# Motor-Z.net
KiCad netlist of a schematic drawn in Altium Designer
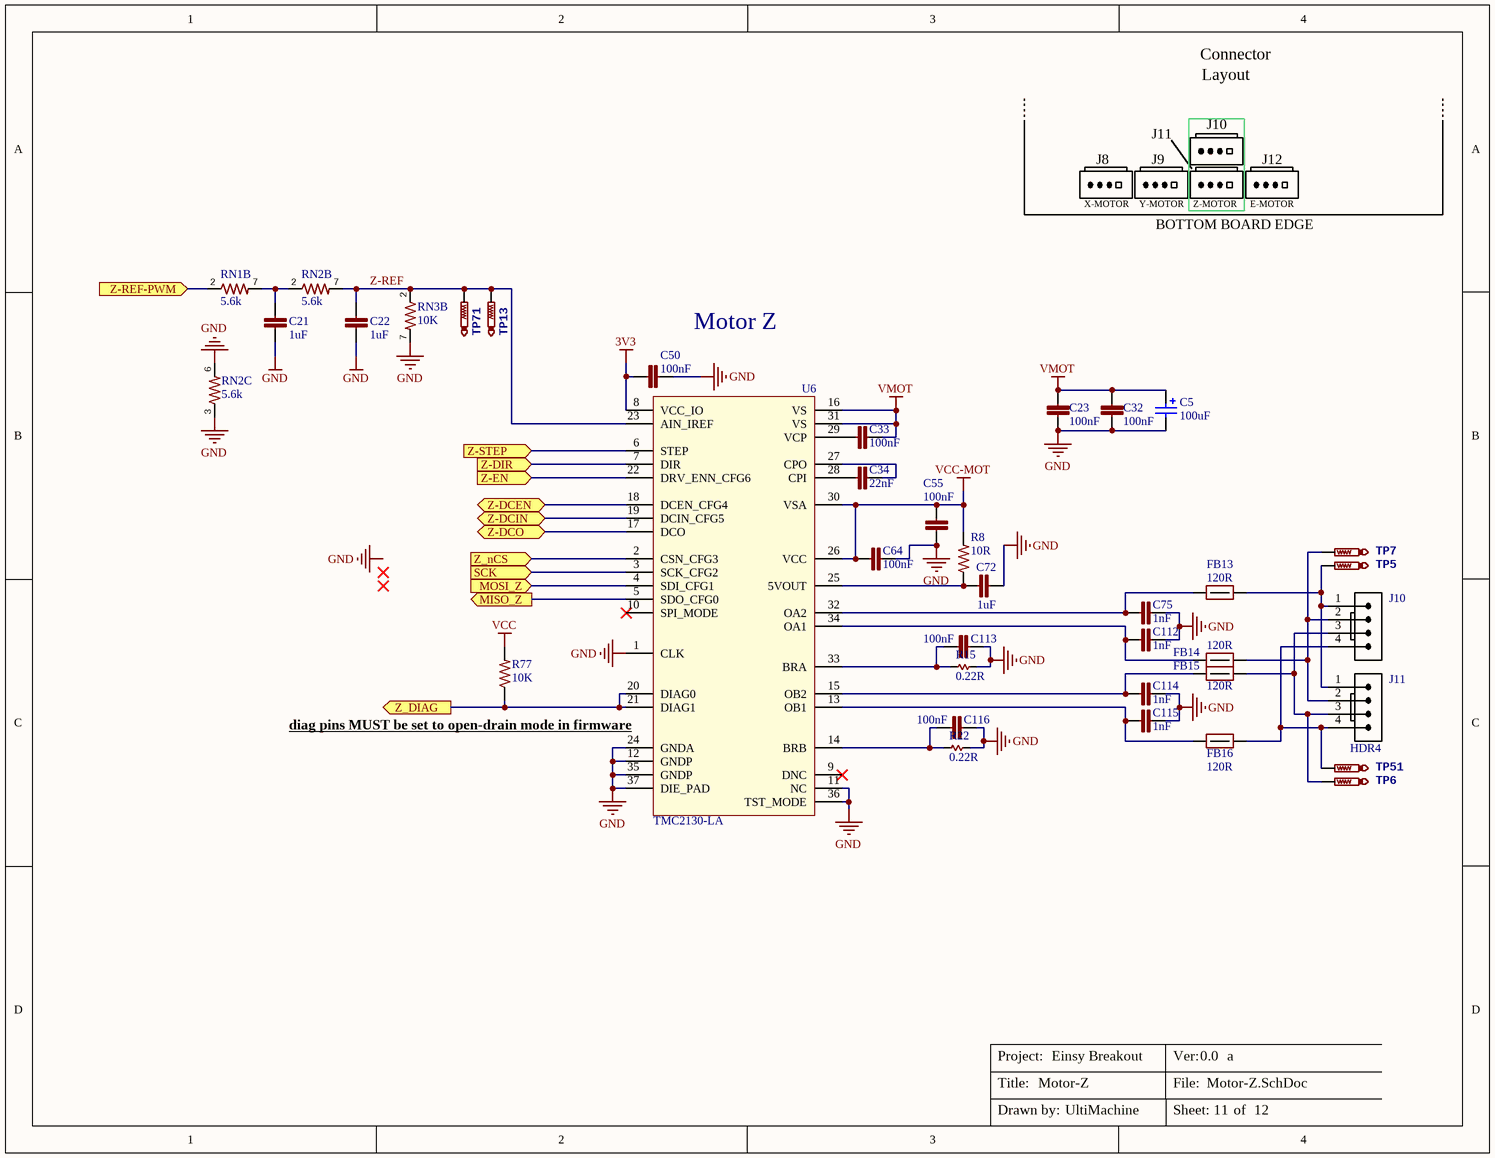
[diagram p0: Motor-Z.SchDoc]

(export (version "E")
  (design (tool "Eeschema 10.0.6"))
  (components
    (comp (ref "C5")
      (value "100uF")
      (footprint "CAP-ELEC-063063077")
      (description "CAP ALUM 100UF 35V 20% SMD")
      (fields (field (name "MANUFACTURER") "Nichicon") (field (name "TOLERANCE") "+/- 20%"))
      (libsource (lib "3Delight") (part "UWT1V101MCL1GS"))
    )
    (comp (ref "C21")
      (value "1uF")
      (footprint "C0402")
      (description "CAP CER 0402 1uF 6.3V 10% X5R")
      (fields (field (name "MANUFACTURER") "Murata") (field (name "TOLERANCE") "+/- 10%"))
      (libsource (lib "3Delight") (part "GRM155R60J105KE19D"))
    )
    (comp (ref "C22")
      (value "1uF")
      (footprint "C0402")
      (description "CAP CER 0402 1uF 6.3V 10% X5R")
      (fields (field (name "MANUFACTURER") "Murata") (field (name "TOLERANCE") "+/- 10%"))
      (libsource (lib "3Delight") (part "GRM155R60J105KE19D"))
    )
    (comp (ref "C23")
      (value "100nF")
      (footprint "C0603")
      (description "CAP CER 0603 100nF 50V 10% X7R")
      (fields (field (name "MANUFACTURER") "Kemet") (field (name "TOLERANCE") "+/- 10%"))
      (libsource (lib "3Delight") (part "C0603C104K5RACTU"))
    )
    (comp (ref "C32")
      (value "100nF")
      (footprint "C0603")
      (description "CAP CER 0603 100nF 50V 10% X7R")
      (fields (field (name "MANUFACTURER") "Kemet") (field (name "TOLERANCE") "+/- 10%"))
      (libsource (lib "3Delight") (part "C0603C104K5RACTU"))
    )
    (comp (ref "C33")
      (value "100nF")
      (footprint "C0603")
      (description "CAP CER 0603 100nF 50V 10% X7R")
      (fields (field (name "MANUFACTURER") "Kemet") (field (name "TOLERANCE") "+/- 10%"))
      (libsource (lib "") (part "C0603C104K5RACTU_1"))
    )
    (comp (ref "C34")
      (value "22nF")
      (footprint "C0402")
      (description "CAP CER 0402 22nF ±10% 50V X7R")
      (fields (field (name "MANUFACTURER") "YAGEO") (field (name "TOLERANCE") "+/- 10%"))
      (libsource (lib "3Delight") (part "GCM155R71H223KA55D"))
    )
    (comp (ref "C50")
      (value "100nF")
      (footprint "C0402")
      (description "CAP CER 0402 100nF 16V 10% X7R")
      (fields (field (name "MANUFACTURER") "Murata") (field (name "TOLERANCE") "+/- 10%"))
      (libsource (lib "3Delight") (part "GRM155R71C104KA88D"))
    )
    (comp (ref "C55")
      (value "100nF")
      (footprint "C0402")
      (description "CAP CER 0402 100nF 16V 10% X7R")
      (fields (field (name "MANUFACTURER") "Murata") (field (name "TOLERANCE") "+/- 10%"))
      (libsource (lib "") (part "GRM155R71C104KA88D_1"))
    )
    (comp (ref "C64")
      (value "100nF")
      (footprint "C0402")
      (description "CAP CER 0402 100nF 16V 10% X7R")
      (fields (field (name "MANUFACTURER") "Murata") (field (name "TOLERANCE") "+/- 10%"))
      (libsource (lib "3Delight") (part "GRM155R71C104KA88D"))
    )
    (comp (ref "C72")
      (value "1uF")
      (footprint "C0402")
      (description "CAP CER 0402 1uF 6.3V 10% X5R")
      (fields (field (name "MANUFACTURER") "Murata") (field (name "TOLERANCE") "+/- 10%"))
      (libsource (lib "") (part "GRM155R60J105KE19D_1"))
    )
    (comp (ref "C75")
      (value "1nF")
      (footprint "C0603")
      (description "CAP CER 0603  1nF 50v 10% X7R")
      (fields (field (name "MANUFACTURER") "Kemet") (field (name "TOLERANCE") "+/- 10%"))
      (libsource (lib "3Delight") (part "C0603C102K5RACTU"))
    )
    (comp (ref "C112")
      (value "1nF")
      (footprint "C0603")
      (description "CAP CER 0603  1nF 50v 10% X7R")
      (fields (field (name "MANUFACTURER") "Kemet") (field (name "TOLERANCE") "+/- 10%"))
      (libsource (lib "3Delight") (part "C0603C102K5RACTU"))
    )
    (comp (ref "C113")
      (value "100nF")
      (footprint "C0603")
      (description "CAP CER 0603 100nF 50V 10% X7R")
      (fields (field (name "MANUFACTURER") "Kemet") (field (name "TOLERANCE") "+/- 10%"))
      (libsource (lib "") (part "C0603C104K5RACTU_2"))
    )
    (comp (ref "C114")
      (value "1nF")
      (footprint "C0603")
      (description "CAP CER 0603  1nF 50v 10% X7R")
      (fields (field (name "MANUFACTURER") "Kemet") (field (name "TOLERANCE") "+/- 10%"))
      (libsource (lib "3Delight") (part "C0603C102K5RACTU"))
    )
    (comp (ref "C115")
      (value "1nF")
      (footprint "C0603")
      (description "CAP CER 0603  1nF 50v 10% X7R")
      (fields (field (name "MANUFACTURER") "Kemet") (field (name "TOLERANCE") "+/- 10%"))
      (libsource (lib "3Delight") (part "C0603C102K5RACTU"))
    )
    (comp (ref "C116")
      (value "100nF")
      (footprint "C0603")
      (description "CAP CER 0603 100nF 50V 10% X7R")
      (fields (field (name "MANUFACTURER") "Kemet") (field (name "TOLERANCE") "+/- 10%"))
      (libsource (lib "") (part "C0603C104K5RACTU_2"))
    )
    (comp (ref "FB13")
      (value "120R")
      (footprint "FB0603")
      (description "FERRITE BEAD 120 OHM 0603 1LN")
      (fields (field (name "MANUFACTURER") "Samsung") (field (name "PART") "FERRITE 120R 3A 0603"))
      (libsource (lib "Inductors") (part "FERRITE 120R 3A 0603"))
    )
    (comp (ref "FB14")
      (value "120R")
      (footprint "FB0603")
      (description "FERRITE BEAD 120 OHM 0603 1LN")
      (fields (field (name "MANUFACTURER") "Samsung") (field (name "PART") "FERRITE 120R 3A 0603"))
      (libsource (lib "Inductors") (part "FERRITE 120R 3A 0603"))
    )
    (comp (ref "FB15")
      (value "120R")
      (footprint "FB0603")
      (description "FERRITE BEAD 120 OHM 0603 1LN")
      (fields (field (name "MANUFACTURER") "Samsung") (field (name "PART") "FERRITE 120R 3A 0603"))
      (libsource (lib "Inductors") (part "FERRITE 120R 3A 0603"))
    )
    (comp (ref "FB16")
      (value "120R")
      (footprint "FB0603")
      (description "FERRITE BEAD 120 OHM 0603 1LN")
      (fields (field (name "MANUFACTURER") "Samsung") (field (name "PART") "FERRITE 120R 3A 0603"))
      (libsource (lib "Inductors") (part "FERRITE 120R 3A 0603"))
    )
    (comp (ref "J10")
      (value "Molex 0705430003")
      (footprint "4POL254")
      (description "Molex 4 Pin Clip Connector")
      (fields (field (name "MANUFACTURER") "Molex") (field (name "PART") "4 Pin Conn"))
      (libsource (lib "3Delight") (part "CONN 4PIN 0.1{dblquote} VERT SHRD LOCK ALT"))
    )
    (comp (ref "J11")
      (value "HDR4")
      (footprint "4POL254")
      (description "Molex 4 Pin Clip Connector")
      (fields (field (name "MANUFACTURER") "Molex") (field (name "PART") "4 Pin Conn"))
      (libsource (lib "3Delight") (part "CONN 4PIN 0.1{dblquote} VERT SHRD LOCK ALT"))
    )
    (comp (ref "R8")
      (value "10R")
      (footprint "R0402")
      (description "RES SMD 10 OHM 1% 1/16W 0402")
      (fields (field (name "MANUFACTURER") "Yageo") (field (name "TOLERANCE") "+/- 1%"))
      (libsource (lib "3Delight") (part "RC0402FR-0710RL"))
    )
    (comp (ref "R15")
      (value "0.22R")
      (footprint "R1206")
      (description "RES SMD 0.22 OHM 1% 1/3W 1206")
      (fields (field (name "MANUFACTURER") "Panasonic") (field (name "TOLERANCE") "+/- 1%"))
      (libsource (lib "Resistors") (part "0.22R 1% 1206"))
    )
    (comp (ref "R22")
      (value "0.22R")
      (footprint "R1206")
      (description "RES SMD 0.22 OHM 1% 1/3W 1206")
      (fields (field (name "MANUFACTURER") "Panasonic") (field (name "TOLERANCE") "+/- 1%"))
      (libsource (lib "Resistors") (part "0.22R 1% 1206"))
    )
    (comp (ref "R77")
      (value "10K")
      (footprint "R0402")
      (description "RES SMD 10K OHM 1% 1/16W 0402")
      (fields (field (name "MANUFACTURER") "Yageo") (field (name "PART") "10k 1% 0402"))
      (libsource (lib "3Delight") (part "RC0402FR-0710KP"))
    )
    (comp (ref "RN1")
      (value "5.6k")
      (footprint "CAY16")
      (description "RES ARRAY 4 RES 5.6K OHM 1206")
      (fields (field (name "MANUFACTURER") "Bourns") (field (name "TOLERANCE") "+/- 5%"))
      (libsource (lib "Resistors") (part "5.6k x 4 5% 1206"))
    )
    (comp (ref "RN2")
      (value "5.6k")
      (footprint "CAY16")
      (description "RES ARRAY 4 RES 5.6K OHM 1206")
      (fields (field (name "MANUFACTURER") "Bourns") (field (name "TOLERANCE") "+/- 5%"))
      (libsource (lib "Resistors") (part "5.6k x 4 5% 1206"))
    )
    (comp (ref "RN3")
      (value "10K")
      (footprint "CAY16")
      (description "RES ARRAY 4 RES 10K 1206 62.5mW 5%")
      (fields (field (name "MANUFACTURER") "Bourns") (field (name "TOLERANCE") "+/- 5%"))
      (libsource (lib "3Delight") (part "CAY16-103J4LF"))
    )
    (comp (ref "TP5")
      (value "TestPoint")
      (footprint "TP1-27")
      (description "Test Point")
      (libsource (lib "") (part "TestPoint_1"))
    )
    (comp (ref "TP6")
      (value "TestPoint")
      (footprint "TP1-27")
      (description "Test Point")
      (libsource (lib "") (part "TestPoint_1"))
    )
    (comp (ref "TP7")
      (value "TestPoint")
      (footprint "TP1-27")
      (description "Test Point")
      (libsource (lib "") (part "TestPoint_1"))
    )
    (comp (ref "TP13")
      (value "TestPoint")
      (footprint "TP1-27")
      (description "Test Point")
      (libsource (lib "3Delight") (part "TestPoint"))
    )
    (comp (ref "TP51")
      (value "TestPoint")
      (footprint "TP1-27")
      (description "Test Point")
      (libsource (lib "") (part "TestPoint_1"))
    )
    (comp (ref "TP71")
      (value "TestPoint")
      (footprint "TP1-27")
      (description "Test Point")
      (libsource (lib "3Delight") (part "TestPoint"))
    )
    (comp (ref "U6")
      (value "TMC2130-LA")
      (footprint "QFN36-50P500X600X900_HS-37N")
      (description "IC STEPPER MOTOR DVR SPI 36QFN")
      (fields (field (name "MANUFACTURER") "Trinamic") (field (name "PART") "TMC2130"))
      (libsource (lib "ICs-Motor Controller") (part "TMC2130-LA-T"))
    )
  )
  (nets
    (net (code "1") (name "/MISO_Z") (class "Default")
      (node (ref "U6") (pin "5") (pinfunction "SDO_CFG0_5") (pintype "passive"))
    )
    (net (code "2") (name "/MOSI_Z") (class "Default")
      (node (ref "U6") (pin "4") (pinfunction "SDI_CFG1_4") (pintype "passive"))
    )
    (net (code "3") (name "/SCK") (class "Default")
      (node (ref "U6") (pin "3") (pinfunction "SCK_CFG2_3") (pintype "passive"))
    )
    (net (code "4") (name "/Z-DCEN") (class "Default")
      (node (ref "U6") (pin "18") (pinfunction "DCEN_CFG4_18") (pintype "passive"))
    )
    (net (code "5") (name "/Z-DCIN") (class "Default")
      (node (ref "U6") (pin "19") (pinfunction "DCIN_CFG5_19") (pintype "passive"))
    )
    (net (code "6") (name "/Z-DCO") (class "Default")
      (node (ref "U6") (pin "17") (pinfunction "DCO_17") (pintype "passive"))
    )
    (net (code "7") (name "/Z-DIR") (class "Default")
      (node (ref "U6") (pin "7") (pinfunction "DIR_7") (pintype "passive"))
    )
    (net (code "8") (name "/Z-EN") (class "Default")
      (node (ref "U6") (pin "22") (pinfunction "DRV_ENN_CFG6_22") (pintype "passive"))
    )
    (net (code "9") (name "/Z-REF") (class "Default")
      (node (ref "C22") (pin "1") (pinfunction "1_1") (pintype "passive"))
      (node (ref "RN2") (pin "7") (pinfunction "2_7") (pintype "passive"))
      (node (ref "RN3") (pin "2") (pinfunction "1_2") (pintype "passive"))
      (node (ref "TP13") (pin "TP") (pinfunction "TP_TP") (pintype "passive"))
      (node (ref "TP71") (pin "TP") (pinfunction "TP_TP") (pintype "passive"))
      (node (ref "U6") (pin "23") (pinfunction "AIN_IREF_23") (pintype "passive"))
    )
    (net (code "10") (name "/Z-REF-PWM") (class "Default")
      (node (ref "RN1") (pin "2") (pinfunction "1_2") (pintype "passive"))
    )
    (net (code "11") (name "/Z-STEP") (class "Default")
      (node (ref "U6") (pin "6") (pinfunction "STEP_6") (pintype "passive"))
    )
    (net (code "12") (name "/Z_DIAG") (class "Default")
      (node (ref "R77") (pin "1") (pinfunction "1_1") (pintype "passive"))
      (node (ref "U6") (pin "20") (pinfunction "DIAG0_20") (pintype "passive"))
      (node (ref "U6") (pin "21") (pinfunction "DIAG1_21") (pintype "passive"))
    )
    (net (code "13") (name "/Z_nCS") (class "Default")
      (node (ref "U6") (pin "2") (pinfunction "CSN_CFG3_2") (pintype "passive"))
    )
    (net (code "14") (name "3V3") (class "Default")
      (node (ref "C50") (pin "2") (pinfunction "2_2") (pintype "passive"))
      (node (ref "U6") (pin "8") (pinfunction "VCC_IO_8") (pintype "passive"))
    )
    (net (code "15") (name "GND") (class "Default")
      (node (ref "C112") (pin "2") (pinfunction "2_2") (pintype "passive"))
      (node (ref "C113") (pin "1") (pinfunction "1_1") (pintype "passive"))
      (node (ref "C114") (pin "2") (pinfunction "2_2") (pintype "passive"))
      (node (ref "C115") (pin "2") (pinfunction "2_2") (pintype "passive"))
      (node (ref "C116") (pin "1") (pinfunction "1_1") (pintype "passive"))
      (node (ref "C21") (pin "2") (pinfunction "2_2") (pintype "passive"))
      (node (ref "C22") (pin "2") (pinfunction "2_2") (pintype "passive"))
      (node (ref "C23") (pin "1") (pinfunction "1_1") (pintype "passive"))
      (node (ref "C32") (pin "1") (pinfunction "1_1") (pintype "passive"))
      (node (ref "C5") (pin "2") (pinfunction "2_2") (pintype "passive"))
      (node (ref "C50") (pin "1") (pinfunction "1_1") (pintype "passive"))
      (node (ref "C55") (pin "1") (pinfunction "1_1") (pintype "passive"))
      (node (ref "C64") (pin "1") (pinfunction "1_1") (pintype "passive"))
      (node (ref "C72") (pin "2") (pinfunction "2_2") (pintype "passive"))
      (node (ref "C75") (pin "2") (pinfunction "2_2") (pintype "passive"))
      (node (ref "R15") (pin "2") (pinfunction "2_2") (pintype "passive"))
      (node (ref "R22") (pin "2") (pinfunction "2_2") (pintype "passive"))
      (node (ref "RN2") (pin "3") (pinfunction "1_3") (pintype "passive"))
      (node (ref "RN2") (pin "6") (pinfunction "2_6") (pintype "passive"))
      (node (ref "RN3") (pin "7") (pinfunction "2_7") (pintype "passive"))
      (node (ref "U6") (pin "1") (pinfunction "CLK_1") (pintype "passive"))
      (node (ref "U6") (pin "11") (pinfunction "NC_11") (pintype "passive"))
      (node (ref "U6") (pin "12") (pinfunction "GNDP_12") (pintype "passive"))
      (node (ref "U6") (pin "24") (pinfunction "GNDA_24") (pintype "passive"))
      (node (ref "U6") (pin "35") (pinfunction "GNDP_35") (pintype "passive"))
      (node (ref "U6") (pin "36") (pinfunction "TST_MODE_36") (pintype "passive"))
      (node (ref "U6") (pin "37") (pinfunction "DIE_PAD_37") (pintype "passive"))
    )
    (net (code "16") (name "Net-(FB13-Pad2)") (class "Default")
      (node (ref "FB13") (pin "2") (pinfunction "2_2") (pintype "passive"))
      (node (ref "J10") (pin "1") (pinfunction "1_1") (pintype "passive"))
      (node (ref "J11") (pin "1") (pinfunction "1_1") (pintype "passive"))
      (node (ref "TP5") (pin "TP") (pinfunction "TP_TP") (pintype "passive"))
    )
    (net (code "17") (name "Net-(FB14-Pad2)") (class "Default")
      (node (ref "FB14") (pin "2") (pinfunction "2_2") (pintype "passive"))
      (node (ref "J10") (pin "2") (pinfunction "2_2") (pintype "passive"))
      (node (ref "J11") (pin "2") (pinfunction "2_2") (pintype "passive"))
      (node (ref "TP7") (pin "TP") (pinfunction "TP_TP") (pintype "passive"))
    )
    (net (code "18") (name "Net-(FB15-Pad2)") (class "Default")
      (node (ref "FB15") (pin "2") (pinfunction "2_2") (pintype "passive"))
      (node (ref "J10") (pin "3") (pinfunction "3_3") (pintype "passive"))
      (node (ref "J11") (pin "3") (pinfunction "3_3") (pintype "passive"))
      (node (ref "TP6") (pin "TP") (pinfunction "TP_TP") (pintype "passive"))
    )
    (net (code "19") (name "Net-(FB16-Pad2)") (class "Default")
      (node (ref "FB16") (pin "2") (pinfunction "2_2") (pintype "passive"))
      (node (ref "J10") (pin "4") (pinfunction "4_4") (pintype "passive"))
      (node (ref "J11") (pin "4") (pinfunction "4_4") (pintype "passive"))
      (node (ref "TP51") (pin "TP") (pinfunction "TP_TP") (pintype "passive"))
    )
    (net (code "20") (name "Net-(RN1B-2)") (class "Default")
      (node (ref "C21") (pin "1") (pinfunction "1_1") (pintype "passive"))
      (node (ref "RN1") (pin "7") (pinfunction "2_7") (pintype "passive"))
      (node (ref "RN2") (pin "2") (pinfunction "1_2") (pintype "passive"))
    )
    (net (code "21") (name "Net-(U6-5VOUT)") (class "Default")
      (node (ref "C72") (pin "1") (pinfunction "1_1") (pintype "passive"))
      (node (ref "R8") (pin "1") (pinfunction "1_1") (pintype "passive"))
      (node (ref "U6") (pin "25") (pinfunction "5VOUT_25") (pintype "passive"))
    )
    (net (code "22") (name "Net-(U6-BRA)") (class "Default")
      (node (ref "C113") (pin "2") (pinfunction "2_2") (pintype "passive"))
      (node (ref "R15") (pin "1") (pinfunction "1_1") (pintype "passive"))
      (node (ref "U6") (pin "33") (pinfunction "BRA_33") (pintype "passive"))
    )
    (net (code "23") (name "Net-(U6-BRB)") (class "Default")
      (node (ref "C116") (pin "2") (pinfunction "2_2") (pintype "passive"))
      (node (ref "R22") (pin "1") (pinfunction "1_1") (pintype "passive"))
      (node (ref "U6") (pin "14") (pinfunction "BRB_14") (pintype "passive"))
    )
    (net (code "24") (name "Net-(U6-CPI)") (class "Default")
      (node (ref "C34") (pin "1") (pinfunction "1_1") (pintype "passive"))
      (node (ref "U6") (pin "28") (pinfunction "CPI_28") (pintype "passive"))
    )
    (net (code "25") (name "Net-(U6-CPO)") (class "Default")
      (node (ref "C34") (pin "2") (pinfunction "2_2") (pintype "passive"))
      (node (ref "U6") (pin "27") (pinfunction "CPO_27") (pintype "passive"))
    )
    (net (code "26") (name "Net-(U6-OA1)") (class "Default")
      (node (ref "C112") (pin "1") (pinfunction "1_1") (pintype "passive"))
      (node (ref "FB14") (pin "1") (pinfunction "1_1") (pintype "passive"))
      (node (ref "U6") (pin "34") (pinfunction "OA1_34") (pintype "passive"))
    )
    (net (code "27") (name "Net-(U6-OA2)") (class "Default")
      (node (ref "C75") (pin "1") (pinfunction "1_1") (pintype "passive"))
      (node (ref "FB13") (pin "1") (pinfunction "1_1") (pintype "passive"))
      (node (ref "U6") (pin "32") (pinfunction "OA2_32") (pintype "passive"))
    )
    (net (code "28") (name "Net-(U6-OB1)") (class "Default")
      (node (ref "C115") (pin "1") (pinfunction "1_1") (pintype "passive"))
      (node (ref "FB16") (pin "1") (pinfunction "1_1") (pintype "passive"))
      (node (ref "U6") (pin "13") (pinfunction "OB1_13") (pintype "passive"))
    )
    (net (code "29") (name "Net-(U6-OB2)") (class "Default")
      (node (ref "C114") (pin "1") (pinfunction "1_1") (pintype "passive"))
      (node (ref "FB15") (pin "1") (pinfunction "1_1") (pintype "passive"))
      (node (ref "U6") (pin "15") (pinfunction "OB2_15") (pintype "passive"))
    )
    (net (code "30") (name "Net-(U6-VCP)") (class "Default")
      (node (ref "C33") (pin "1") (pinfunction "1_1") (pintype "passive"))
      (node (ref "U6") (pin "29") (pinfunction "VCP_29") (pintype "passive"))
    )
    (net (code "31") (name "VCC") (class "Default")
      (node (ref "R77") (pin "2") (pinfunction "2_2") (pintype "passive"))
    )
    (net (code "32") (name "VCC-MOT") (class "Default")
      (node (ref "C55") (pin "2") (pinfunction "2_2") (pintype "passive"))
      (node (ref "C64") (pin "2") (pinfunction "2_2") (pintype "passive"))
      (node (ref "R8") (pin "2") (pinfunction "2_2") (pintype "passive"))
      (node (ref "U6") (pin "26") (pinfunction "VCC_26") (pintype "passive"))
      (node (ref "U6") (pin "30") (pinfunction "VSA_30") (pintype "passive"))
    )
    (net (code "33") (name "VMOT") (class "Default")
      (node (ref "C23") (pin "2") (pinfunction "2_2") (pintype "passive"))
      (node (ref "C32") (pin "2") (pinfunction "2_2") (pintype "passive"))
      (node (ref "C33") (pin "2") (pinfunction "2_2") (pintype "passive"))
      (node (ref "C5") (pin "1") (pinfunction "1_1") (pintype "passive"))
      (node (ref "U6") (pin "16") (pinfunction "VS_16") (pintype "passive"))
      (node (ref "U6") (pin "31") (pinfunction "VS_31") (pintype "passive"))
    )
    (net (code "34") (name "unconnected-(U6-DNC-Pad9)") (class "Default")
      (node (ref "U6") (pin "9") (pinfunction "DNC_9") (pintype "passive+no_connect"))
    )
    (net (code "35") (name "unconnected-(U6-SPI_MODE-Pad10)") (class "Default")
      (node (ref "U6") (pin "10") (pinfunction "SPI_MODE_10") (pintype "passive+no_connect"))
    )
  )
)
